# ETHERNET.net
KiCad netlist of a schematic drawn in Altium Designer
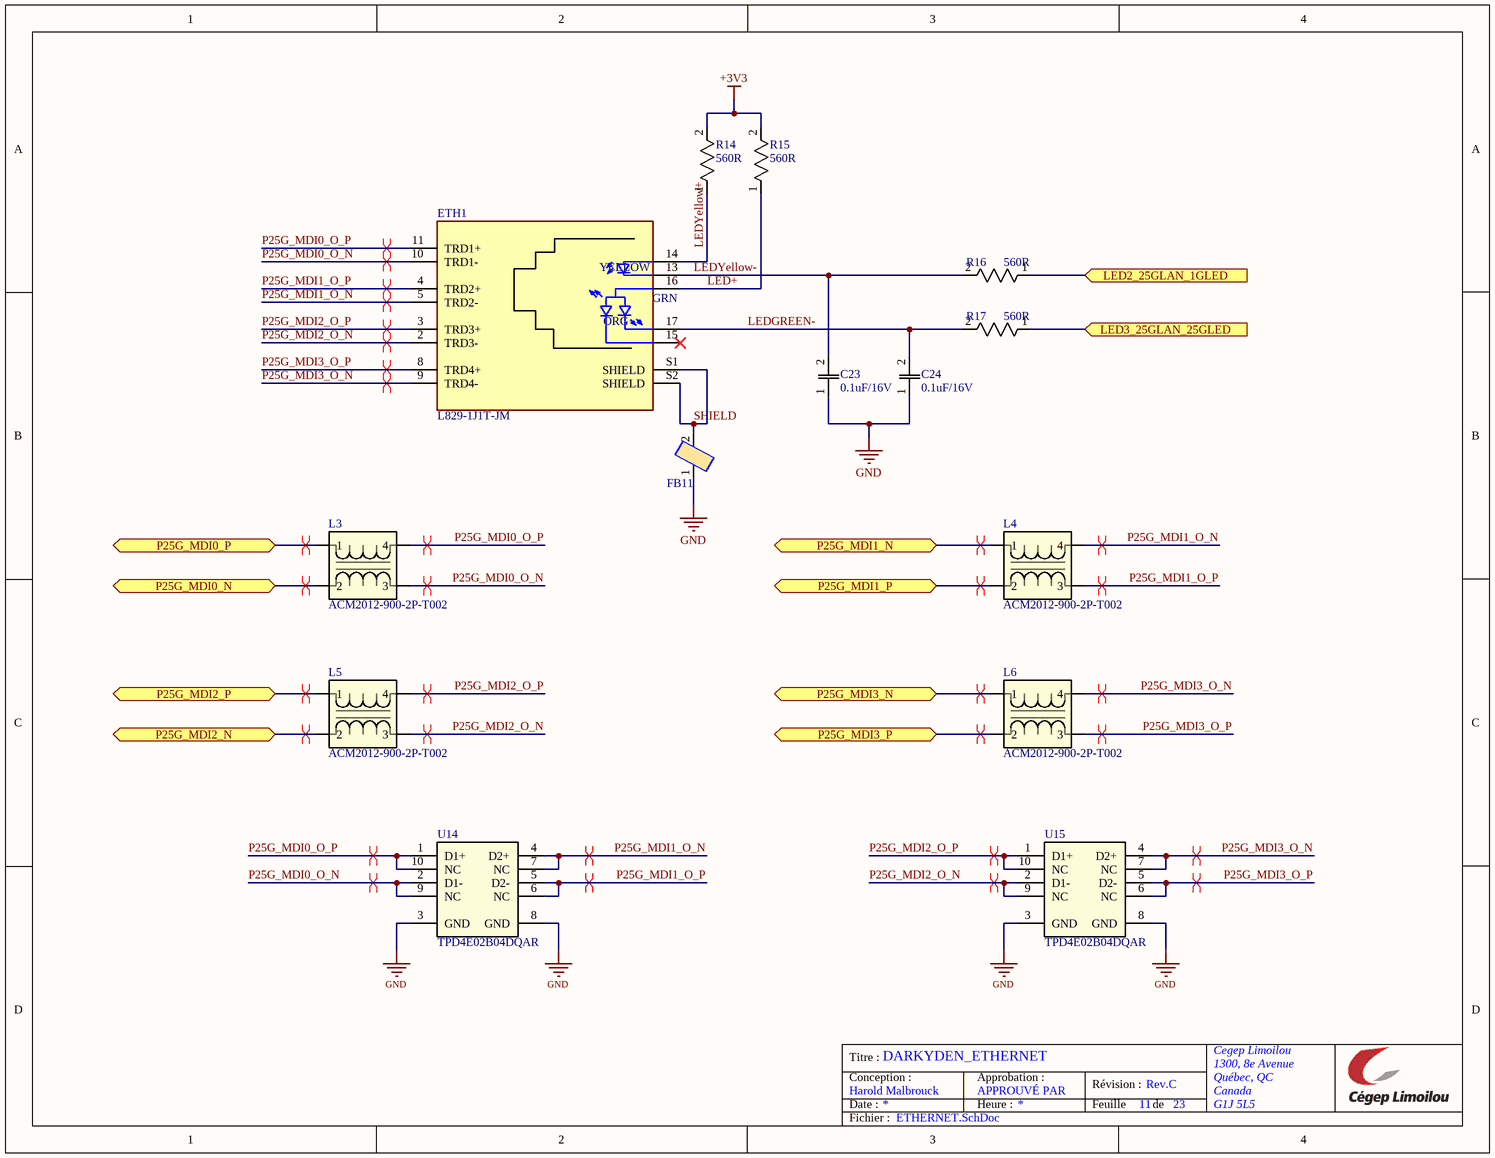
[diagram p0: ETHERNET.SchDoc]

(export (version "E")
  (design (tool "Eeschema 10.0.6"))
  (components
    (comp (ref "C23")
      (value "0.1uF/16V")
      (footprint "C0805")
      (description "0.1uF/16V ±10% X7R 0805 (2012METRIC) Ceramic Capacitor SMD Auto X7R")
      (fields
        (field (name "MANUFACTURER") "KEMET")
        (field (name "MANUFACTURER PART NUMBER") "C0805C104K4RACAUTO")
      )
      (libsource (lib "DARKYDEN") (part "C0805C104K4RACAUTO"))
    )
    (comp (ref "C24")
      (value "0.1uF/16V")
      (footprint "C0805")
      (description "0.1uF/16V ±10% X7R 0805 (2012METRIC) Ceramic Capacitor SMD Auto X7R")
      (fields
        (field (name "MANUFACTURER") "KEMET")
        (field (name "MANUFACTURER PART NUMBER") "C0805C104K4RACAUTO")
      )
      (libsource (lib "DARKYDEN") (part "C0805C104K4RACAUTO"))
    )
    (comp (ref "ETH1")
      (value "L829-1J1T-JM")
      (footprint "RJ-45")
      (description "Modular Connectors / Ethernet Connectors 1x1 2.5GBT MagJack")
      (fields
        (field (name "DIGI-KEY_PART_NUMBER") "507-2068-ND")
        (field (name "MF") "Bel Magnetic Solutions")
      )
      (libsource (lib "L829-1J1T-JM") (part "L829-1J1T-JM"))
    )
    (comp (ref "FB11")
      (value "220R / 100MHz")
      (footprint "SamacSys:BLM18SP221SN1B")
      (description "Ferrite Beads Multi-Layer 220Ohm 25% 100MHz 2A 50mOhm DCR 0603 Paper T/R")
      (fields
        (field (name "MANUFACTURER_PART_NUMBER") "BLM18EG221SN1D")
        (field (name "MOUSER PART NUMBER") "81-BLM18EG221SN1D")
      )
      (libsource (lib "SamacSys") (part "BLM18EG221SN1D"))
    )
    (comp (ref "L3")
      (value "ACM2012-900-2P-T002")
      (footprint "SamacSys:ACM20129002PT002")
      (description "Ferrite Beads Wirewound Common Mode Filter 90Ohm 100MHz 400mA 0805 T/R")
      (fields (field (name "MOUSER PART NUMBER") "810-ACM20129002PT002") (field (name "MANUFACTURER") "TDK"))
      (libsource (lib "SamacSys") (part "ACM2012-900-2P-T002"))
    )
    (comp (ref "L4")
      (value "ACM2012-900-2P-T002")
      (footprint "SamacSys:ACM20129002PT002")
      (description "Ferrite Beads Wirewound Common Mode Filter 90Ohm 100MHz 400mA 0805 T/R")
      (fields (field (name "MOUSER PART NUMBER") "810-ACM20129002PT002") (field (name "MANUFACTURER") "TDK"))
      (libsource (lib "SamacSys") (part "ACM2012-900-2P-T002"))
    )
    (comp (ref "L5")
      (value "ACM2012-900-2P-T002")
      (footprint "SamacSys:ACM20129002PT002")
      (description "Ferrite Beads Wirewound Common Mode Filter 90Ohm 100MHz 400mA 0805 T/R")
      (fields (field (name "MOUSER PART NUMBER") "810-ACM20129002PT002") (field (name "MANUFACTURER") "TDK"))
      (libsource (lib "SamacSys") (part "ACM2012-900-2P-T002"))
    )
    (comp (ref "L6")
      (value "ACM2012-900-2P-T002")
      (footprint "SamacSys:ACM20129002PT002")
      (description "Ferrite Beads Wirewound Common Mode Filter 90Ohm 100MHz 400mA 0805 T/R")
      (fields (field (name "MOUSER PART NUMBER") "810-ACM20129002PT002") (field (name "MANUFACTURER") "TDK"))
      (libsource (lib "SamacSys") (part "ACM2012-900-2P-T002"))
    )
    (comp (ref "R14")
      (value "560R")
      (footprint "RESC1608X55N")
      (description "560 Ohm, ï¿½ 1%, 100 mW, 0603 [1608 Metric], Thick Film, Precision")
      (fields
        (field (name "MANUFACTURER") "Panasonic")
        (field (name "MANUFACTURER PART NUMBER") "ERJ-3EKF5600V")
      )
      (libsource (lib "DARKYDEN") (part "ERJ-3EKF5600V"))
    )
    (comp (ref "R15")
      (value "560R")
      (footprint "RESC1608X55N")
      (description "560 Ohm, ï¿½ 1%, 100 mW, 0603 [1608 Metric], Thick Film, Precision")
      (fields
        (field (name "MANUFACTURER") "Panasonic")
        (field (name "MANUFACTURER PART NUMBER") "ERJ-3EKF5600V")
      )
      (libsource (lib "DARKYDEN") (part "ERJ-3EKF5600V"))
    )
    (comp (ref "R16")
      (value "560R")
      (footprint "RESC1608X55N")
      (description "560 Ohm, ï¿½ 1%, 100 mW, 0603 [1608 Metric], Thick Film, Precision")
      (fields
        (field (name "MANUFACTURER") "Panasonic")
        (field (name "MANUFACTURER PART NUMBER") "ERJ-3EKF5600V")
      )
      (libsource (lib "DARKYDEN") (part "ERJ-3EKF5600V"))
    )
    (comp (ref "R17")
      (value "560R")
      (footprint "RESC1608X55N")
      (description "560 Ohm, ï¿½ 1%, 100 mW, 0603 [1608 Metric], Thick Film, Precision")
      (fields
        (field (name "MANUFACTURER") "Panasonic")
        (field (name "MANUFACTURER PART NUMBER") "ERJ-3EKF5600V")
      )
      (libsource (lib "DARKYDEN") (part "ERJ-3EKF5600V"))
    )
    (comp (ref "U14")
      (value "TPD4E02B04DQAR")
      (footprint "DQA0010A")
      (description "TVS DIODE 3.6V 8.8V 10USON / 4-Channel ESD Protection Diode for USB Type-C and HDMI 2.0")
      (fields (field (name "MANUFACTURER") "Texas Instruments"))
      (libsource (lib "TPD4E02B04DQAR") (part "TPD4E02B04DQAR"))
    )
    (comp (ref "U15")
      (value "TPD4E02B04DQAR")
      (footprint "DQA0010A")
      (description "TVS DIODE 3.6V 8.8V 10USON / 4-Channel ESD Protection Diode for USB Type-C and HDMI 2.0")
      (fields (field (name "MANUFACTURER") "Texas Instruments"))
      (libsource (lib "TPD4E02B04DQAR") (part "TPD4E02B04DQAR"))
    )
  )
  (nets
    (net (code "1") (name "+3V3") (class "Default")
      (node (ref "R14") (pin "2") (pinfunction "2_2") (pintype "passive"))
      (node (ref "R15") (pin "2") (pinfunction "2_2") (pintype "passive"))
    )
    (net (code "2") (name "/LED+") (class "Default")
      (node (ref "ETH1") (pin "16") (pinfunction "CA_16") (pintype "passive"))
      (node (ref "R15") (pin "1") (pinfunction "1_1") (pintype "passive"))
    )
    (net (code "3") (name "/LED2_25GLAN_1GLED") (class "Default")
      (node (ref "R16") (pin "1") (pinfunction "1_1") (pintype "passive"))
    )
    (net (code "4") (name "/LED3_25GLAN_25GLED") (class "Default")
      (node (ref "R17") (pin "1") (pinfunction "1_1") (pintype "passive"))
    )
    (net (code "5") (name "/LEDGREEN-") (class "Default")
      (node (ref "C24") (pin "2") (pinfunction "2_2") (pintype "passive"))
      (node (ref "ETH1") (pin "17") (pinfunction "GK_1_17") (pintype "passive"))
      (node (ref "R17") (pin "2") (pinfunction "2_2") (pintype "passive"))
    )
    (net (code "6") (name "/LEDYellow+") (class "Default")
      (node (ref "ETH1") (pin "14") (pinfunction "YA_1_14") (pintype "passive"))
      (node (ref "R14") (pin "1") (pinfunction "1_1") (pintype "passive"))
    )
    (net (code "7") (name "/LEDYellow-") (class "Default")
      (node (ref "C23") (pin "2") (pinfunction "2_2") (pintype "passive"))
      (node (ref "ETH1") (pin "13") (pinfunction "YK_1_13") (pintype "passive"))
      (node (ref "R16") (pin "2") (pinfunction "2_2") (pintype "passive"))
    )
    (net (code "8") (name "/P25G_MDI0_N") (class "Default")
      (node (ref "L3") (pin "2") (pinfunction "2_2") (pintype "passive"))
    )
    (net (code "9") (name "/P25G_MDI0_O_N") (class "Default")
      (node (ref "ETH1") (pin "10") (pinfunction "TRD1-_10") (pintype "passive"))
      (node (ref "L3") (pin "3") (pinfunction "3_3") (pintype "passive"))
      (node (ref "U14") (pin "2") (pinfunction "D1-_2") (pintype "passive"))
      (node (ref "U14") (pin "9") (pinfunction "NC_9") (pintype "passive"))
    )
    (net (code "10") (name "/P25G_MDI0_O_P") (class "Default")
      (node (ref "ETH1") (pin "11") (pinfunction "TRD1+_11") (pintype "passive"))
      (node (ref "L3") (pin "4") (pinfunction "4_4") (pintype "passive"))
      (node (ref "U14") (pin "1") (pinfunction "D1+_1") (pintype "passive"))
      (node (ref "U14") (pin "10") (pinfunction "NC_10") (pintype "passive"))
    )
    (net (code "11") (name "/P25G_MDI0_P") (class "Default")
      (node (ref "L3") (pin "1") (pinfunction "1_1") (pintype "passive"))
    )
    (net (code "12") (name "/P25G_MDI1_N") (class "Default")
      (node (ref "L4") (pin "1") (pinfunction "1_1") (pintype "passive"))
    )
    (net (code "13") (name "/P25G_MDI1_O_N") (class "Default")
      (node (ref "ETH1") (pin "5") (pinfunction "TRD2-_5") (pintype "passive"))
      (node (ref "L4") (pin "4") (pinfunction "4_4") (pintype "passive"))
      (node (ref "U14") (pin "4") (pinfunction "D2+_4") (pintype "passive"))
      (node (ref "U14") (pin "7") (pinfunction "NC_7") (pintype "passive"))
    )
    (net (code "14") (name "/P25G_MDI1_O_P") (class "Default")
      (node (ref "ETH1") (pin "4") (pinfunction "TRD2+_4") (pintype "passive"))
      (node (ref "L4") (pin "3") (pinfunction "3_3") (pintype "passive"))
      (node (ref "U14") (pin "5") (pinfunction "D2-_5") (pintype "passive"))
      (node (ref "U14") (pin "6") (pinfunction "NC_6") (pintype "passive"))
    )
    (net (code "15") (name "/P25G_MDI1_P") (class "Default")
      (node (ref "L4") (pin "2") (pinfunction "2_2") (pintype "passive"))
    )
    (net (code "16") (name "/P25G_MDI2_N") (class "Default")
      (node (ref "L5") (pin "2") (pinfunction "2_2") (pintype "passive"))
    )
    (net (code "17") (name "/P25G_MDI2_O_N") (class "Default")
      (node (ref "ETH1") (pin "2") (pinfunction "TRD3-_2") (pintype "passive"))
      (node (ref "L5") (pin "3") (pinfunction "3_3") (pintype "passive"))
      (node (ref "U15") (pin "2") (pinfunction "D1-_2") (pintype "passive"))
      (node (ref "U15") (pin "9") (pinfunction "NC_9") (pintype "passive"))
    )
    (net (code "18") (name "/P25G_MDI2_O_P") (class "Default")
      (node (ref "ETH1") (pin "3") (pinfunction "TRD3+_3") (pintype "passive"))
      (node (ref "L5") (pin "4") (pinfunction "4_4") (pintype "passive"))
      (node (ref "U15") (pin "1") (pinfunction "D1+_1") (pintype "passive"))
      (node (ref "U15") (pin "10") (pinfunction "NC_10") (pintype "passive"))
    )
    (net (code "19") (name "/P25G_MDI2_P") (class "Default")
      (node (ref "L5") (pin "1") (pinfunction "1_1") (pintype "passive"))
    )
    (net (code "20") (name "/P25G_MDI3_N") (class "Default")
      (node (ref "L6") (pin "1") (pinfunction "1_1") (pintype "passive"))
    )
    (net (code "21") (name "/P25G_MDI3_O_N") (class "Default")
      (node (ref "ETH1") (pin "9") (pinfunction "TRD4-_9") (pintype "passive"))
      (node (ref "L6") (pin "4") (pinfunction "4_4") (pintype "passive"))
      (node (ref "U15") (pin "4") (pinfunction "D2+_4") (pintype "passive"))
      (node (ref "U15") (pin "7") (pinfunction "NC_7") (pintype "passive"))
    )
    (net (code "22") (name "/P25G_MDI3_O_P") (class "Default")
      (node (ref "ETH1") (pin "8") (pinfunction "TRD4+_8") (pintype "passive"))
      (node (ref "L6") (pin "3") (pinfunction "3_3") (pintype "passive"))
      (node (ref "U15") (pin "5") (pinfunction "D2-_5") (pintype "passive"))
      (node (ref "U15") (pin "6") (pinfunction "NC_6") (pintype "passive"))
    )
    (net (code "23") (name "/P25G_MDI3_P") (class "Default")
      (node (ref "L6") (pin "2") (pinfunction "2_2") (pintype "passive"))
    )
    (net (code "24") (name "/SHIELD") (class "Default")
      (node (ref "ETH1") (pin "S1") (pinfunction "SHIELD_S1") (pintype "passive"))
      (node (ref "ETH1") (pin "S2") (pinfunction "SHIELD_S2") (pintype "passive"))
      (node (ref "FB11") (pin "2") (pinfunction "2_2") (pintype "passive"))
    )
    (net (code "25") (name "GND") (class "Default")
      (node (ref "C23") (pin "1") (pinfunction "1_1") (pintype "passive"))
      (node (ref "C24") (pin "1") (pinfunction "1_1") (pintype "passive"))
      (node (ref "FB11") (pin "1") (pinfunction "1_1") (pintype "passive"))
      (node (ref "U14") (pin "3") (pinfunction "GND_3") (pintype "passive"))
      (node (ref "U14") (pin "8") (pinfunction "GND_8") (pintype "passive"))
      (node (ref "U15") (pin "3") (pinfunction "GND_3") (pintype "passive"))
      (node (ref "U15") (pin "8") (pinfunction "GND_8") (pintype "passive"))
    )
    (net (code "26") (name "unconnected-(ETH1-OK_1-Pad15)") (class "Default")
      (node (ref "ETH1") (pin "15") (pinfunction "OK_1_15") (pintype "passive+no_connect"))
    )
    (net (code "27") (name "unconnected-(ETH1-TRCT1-Pad12)") (class "Default")
      (node (ref "ETH1") (pin "12") (pinfunction "TRCT1_12") (pintype "passive"))
    )
    (net (code "28") (name "unconnected-(ETH1-TRCT2-Pad6)") (class "Default")
      (node (ref "ETH1") (pin "6") (pinfunction "TRCT2_6") (pintype "passive"))
    )
    (net (code "29") (name "unconnected-(ETH1-TRCT3-Pad1)") (class "Default")
      (node (ref "ETH1") (pin "1") (pinfunction "TRCT3_1") (pintype "passive"))
    )
    (net (code "30") (name "unconnected-(ETH1-TRCT4-Pad7)") (class "Default")
      (node (ref "ETH1") (pin "7") (pinfunction "TRCT4_7") (pintype "passive"))
    )
  )
)
